# LCD_breakout.net
KiCad netlist of a schematic drawn in EAGLE
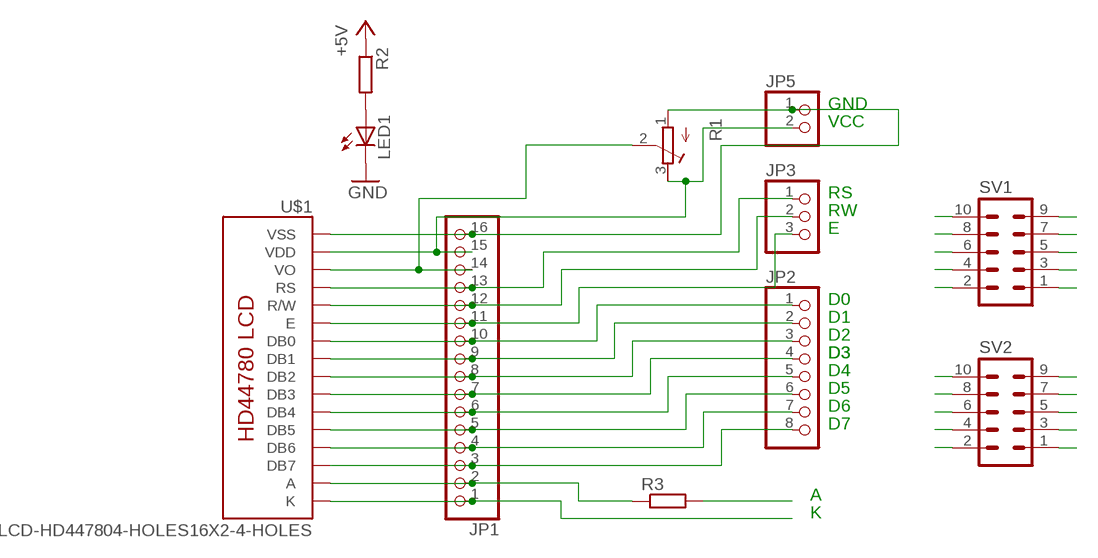
[diagram p0: schematic, sheet 1]

(export (version "E")
  (design (tool "Eeschema 10.0.6"))
  (components
    (comp (ref "JP1")
      (value "PINHD-1X16")
      (footprint "eagle-import:1X16")
      (libsource (lib "eagle-import") (part "PINHD-1X16"))
    )
    (comp (ref "JP2")
      (value "PINHD-1X8")
      (footprint "eagle-import:1X08")
      (libsource (lib "eagle-import") (part "PINHD-1X8"))
    )
    (comp (ref "JP3")
      (value "PINHD-1X3")
      (footprint "eagle-import:1X03")
      (libsource (lib "eagle-import") (part "PINHD-1X3"))
    )
    (comp (ref "JP5")
      (value "PINHD-1X2")
      (footprint "eagle-import:1X02")
      (libsource (lib "eagle-import") (part "PINHD-1X2"))
    )
    (comp (ref "LED1")
      (value "LED3MM")
      (footprint "eagle-import:LED3MM")
      (libsource (lib "eagle-import") (part "LED3MM"))
    )
    (comp (ref "R1")
      (value "R-TRIMM3339P")
      (footprint "eagle-import:RTRIM3339P")
      (libsource (lib "eagle-import") (part "R-TRIMM3339P"))
    )
    (comp (ref "R2")
      (value "R-EU_0204/5")
      (footprint "eagle-import:0204_5")
      (libsource (lib "eagle-import") (part "R-EU_0204/5"))
    )
    (comp (ref "R3")
      (value "R-EU_0204/5")
      (footprint "eagle-import:0204_5")
      (libsource (lib "eagle-import") (part "R-EU_0204/5"))
    )
    (comp (ref "SV1")
      (value "ML10")
      (footprint "eagle-import:ML10")
      (libsource (lib "eagle-import") (part "ML10"))
    )
    (comp (ref "SV2")
      (value "ML10")
      (footprint "eagle-import:ML10")
      (libsource (lib "eagle-import") (part "ML10"))
    )
    (comp (ref "U$1")
      (value "LCD-HD447804-HOLES16X2-4-HOLES")
      (footprint "eagle-import:LCD-16X2-4HOLES")
      (libsource (lib "eagle-import") (part "LCD-HD4478016X2-4-HOLES4-HOLES"))
    )
  )
  (nets
    (net (code "1") (name "+5V") (class "Default")
      (node (ref "JP1") (pin "15") (pinfunction "15_15") (pintype "passive"))
      (node (ref "JP5") (pin "2") (pinfunction "2_2") (pintype "passive"))
      (node (ref "R1") (pin "3") (pinfunction "A_3") (pintype "passive"))
      (node (ref "R2") (pin "1") (pinfunction "1_1") (pintype "passive"))
      (node (ref "R3") (pin "2") (pinfunction "2_2") (pintype "passive"))
      (node (ref "SV1") (pin "9") (pinfunction "9_9") (pintype "passive"))
      (node (ref "SV2") (pin "9") (pinfunction "9_9") (pintype "passive"))
      (node (ref "U$1") (pin "2") (pinfunction "VDD_2") (pintype "power_in"))
    )
    (net (code "2") (name "/D0") (class "Default")
      (node (ref "JP1") (pin "10") (pinfunction "10_10") (pintype "passive"))
      (node (ref "JP2") (pin "1") (pinfunction "1_1") (pintype "passive"))
      (node (ref "SV2") (pin "1") (pinfunction "1_1") (pintype "passive"))
      (node (ref "U$1") (pin "7") (pinfunction "DB0_7") (pintype "bidirectional"))
    )
    (net (code "3") (name "/D1") (class "Default")
      (node (ref "JP1") (pin "9") (pinfunction "9_9") (pintype "passive"))
      (node (ref "JP2") (pin "2") (pinfunction "2_2") (pintype "passive"))
      (node (ref "SV2") (pin "2") (pinfunction "2_2") (pintype "passive"))
      (node (ref "U$1") (pin "8") (pinfunction "DB1_8") (pintype "bidirectional"))
    )
    (net (code "4") (name "/D2") (class "Default")
      (node (ref "JP1") (pin "8") (pinfunction "8_8") (pintype "passive"))
      (node (ref "JP2") (pin "3") (pinfunction "3_3") (pintype "passive"))
      (node (ref "SV2") (pin "3") (pinfunction "3_3") (pintype "passive"))
      (node (ref "U$1") (pin "9") (pinfunction "DB2_9") (pintype "bidirectional"))
    )
    (net (code "5") (name "/D3") (class "Default")
      (node (ref "JP1") (pin "7") (pinfunction "7_7") (pintype "passive"))
      (node (ref "JP2") (pin "4") (pinfunction "4_4") (pintype "passive"))
      (node (ref "SV2") (pin "4") (pinfunction "4_4") (pintype "passive"))
      (node (ref "U$1") (pin "10") (pinfunction "DB3_10") (pintype "bidirectional"))
    )
    (net (code "6") (name "/D4") (class "Default")
      (node (ref "JP1") (pin "6") (pinfunction "6_6") (pintype "passive"))
      (node (ref "JP2") (pin "5") (pinfunction "5_5") (pintype "passive"))
      (node (ref "SV2") (pin "5") (pinfunction "5_5") (pintype "passive"))
      (node (ref "U$1") (pin "11") (pinfunction "DB4_11") (pintype "bidirectional"))
    )
    (net (code "7") (name "/D5") (class "Default")
      (node (ref "JP1") (pin "5") (pinfunction "5_5") (pintype "passive"))
      (node (ref "JP2") (pin "6") (pinfunction "6_6") (pintype "passive"))
      (node (ref "SV2") (pin "6") (pinfunction "6_6") (pintype "passive"))
      (node (ref "U$1") (pin "12") (pinfunction "DB5_12") (pintype "bidirectional"))
    )
    (net (code "8") (name "/D6") (class "Default")
      (node (ref "JP1") (pin "4") (pinfunction "4_4") (pintype "passive"))
      (node (ref "JP2") (pin "7") (pinfunction "7_7") (pintype "passive"))
      (node (ref "SV2") (pin "7") (pinfunction "7_7") (pintype "passive"))
      (node (ref "U$1") (pin "13") (pinfunction "DB6_13") (pintype "bidirectional"))
    )
    (net (code "9") (name "/D7") (class "Default")
      (node (ref "JP1") (pin "3") (pinfunction "3_3") (pintype "passive"))
      (node (ref "JP2") (pin "8") (pinfunction "8_8") (pintype "passive"))
      (node (ref "SV2") (pin "8") (pinfunction "8_8") (pintype "passive"))
      (node (ref "U$1") (pin "14") (pinfunction "DB7_14") (pintype "bidirectional"))
    )
    (net (code "10") (name "/EN") (class "Default")
      (node (ref "JP1") (pin "11") (pinfunction "11_11") (pintype "passive"))
      (node (ref "JP3") (pin "3") (pinfunction "3_3") (pintype "passive"))
      (node (ref "SV1") (pin "3") (pinfunction "3_3") (pintype "passive"))
      (node (ref "U$1") (pin "6") (pinfunction "E_6") (pintype "input"))
    )
    (net (code "11") (name "/RS") (class "Default")
      (node (ref "JP1") (pin "13") (pinfunction "13_13") (pintype "passive"))
      (node (ref "JP3") (pin "1") (pinfunction "1_1") (pintype "passive"))
      (node (ref "SV1") (pin "1") (pinfunction "1_1") (pintype "passive"))
      (node (ref "U$1") (pin "4") (pinfunction "RS_4") (pintype "input"))
    )
    (net (code "12") (name "/RW") (class "Default")
      (node (ref "JP1") (pin "12") (pinfunction "12_12") (pintype "passive"))
      (node (ref "JP3") (pin "2") (pinfunction "2_2") (pintype "passive"))
      (node (ref "SV1") (pin "2") (pinfunction "2_2") (pintype "passive"))
      (node (ref "U$1") (pin "5") (pinfunction "R/W_5") (pintype "input"))
    )
    (net (code "13") (name "GND") (class "Default")
      (node (ref "JP1") (pin "1") (pinfunction "1_1") (pintype "passive"))
      (node (ref "JP1") (pin "16") (pinfunction "16_16") (pintype "passive"))
      (node (ref "JP5") (pin "1") (pinfunction "1_1") (pintype "passive"))
      (node (ref "LED1") (pin "K") (pinfunction "C_K") (pintype "passive"))
      (node (ref "R1") (pin "1") (pinfunction "E_1") (pintype "passive"))
      (node (ref "SV1") (pin "10") (pinfunction "10_10") (pintype "passive"))
      (node (ref "SV2") (pin "10") (pinfunction "10_10") (pintype "passive"))
      (node (ref "U$1") (pin "1") (pinfunction "VSS_1") (pintype "power_in"))
      (node (ref "U$1") (pin "16") (pinfunction "K_16") (pintype "power_in"))
    )
    (net (code "14") (name "Net-(LED1-PadA)") (class "Default")
      (node (ref "LED1") (pin "A") (pinfunction "A_A") (pintype "passive"))
      (node (ref "R2") (pin "2") (pinfunction "2_2") (pintype "passive"))
    )
    (net (code "15") (name "Net-(R1-S)") (class "Default")
      (node (ref "JP1") (pin "14") (pinfunction "14_14") (pintype "passive"))
      (node (ref "R1") (pin "2") (pinfunction "S_2") (pintype "passive"))
      (node (ref "U$1") (pin "3") (pinfunction "VO_3") (pintype "bidirectional"))
    )
    (net (code "16") (name "Net-(U$1-A)") (class "Default")
      (node (ref "JP1") (pin "2") (pinfunction "2_2") (pintype "passive"))
      (node (ref "R3") (pin "1") (pinfunction "1_1") (pintype "passive"))
      (node (ref "U$1") (pin "15") (pinfunction "A_15") (pintype "power_in"))
    )
    (net (code "17") (name "unconnected-(SV1-Pad4)") (class "Default")
      (node (ref "SV1") (pin "4") (pinfunction "4_4") (pintype "passive"))
    )
    (net (code "18") (name "unconnected-(SV1-Pad5)") (class "Default")
      (node (ref "SV1") (pin "5") (pinfunction "5_5") (pintype "passive"))
    )
    (net (code "19") (name "unconnected-(SV1-Pad6)") (class "Default")
      (node (ref "SV1") (pin "6") (pinfunction "6_6") (pintype "passive"))
    )
    (net (code "20") (name "unconnected-(SV1-Pad7)") (class "Default")
      (node (ref "SV1") (pin "7") (pinfunction "7_7") (pintype "passive"))
    )
    (net (code "21") (name "unconnected-(SV1-Pad8)") (class "Default")
      (node (ref "SV1") (pin "8") (pinfunction "8_8") (pintype "passive"))
    )
  )
)
